# RPI-Lora-Gateway-Shield.net
KiCad netlist of a schematic drawn in EAGLE
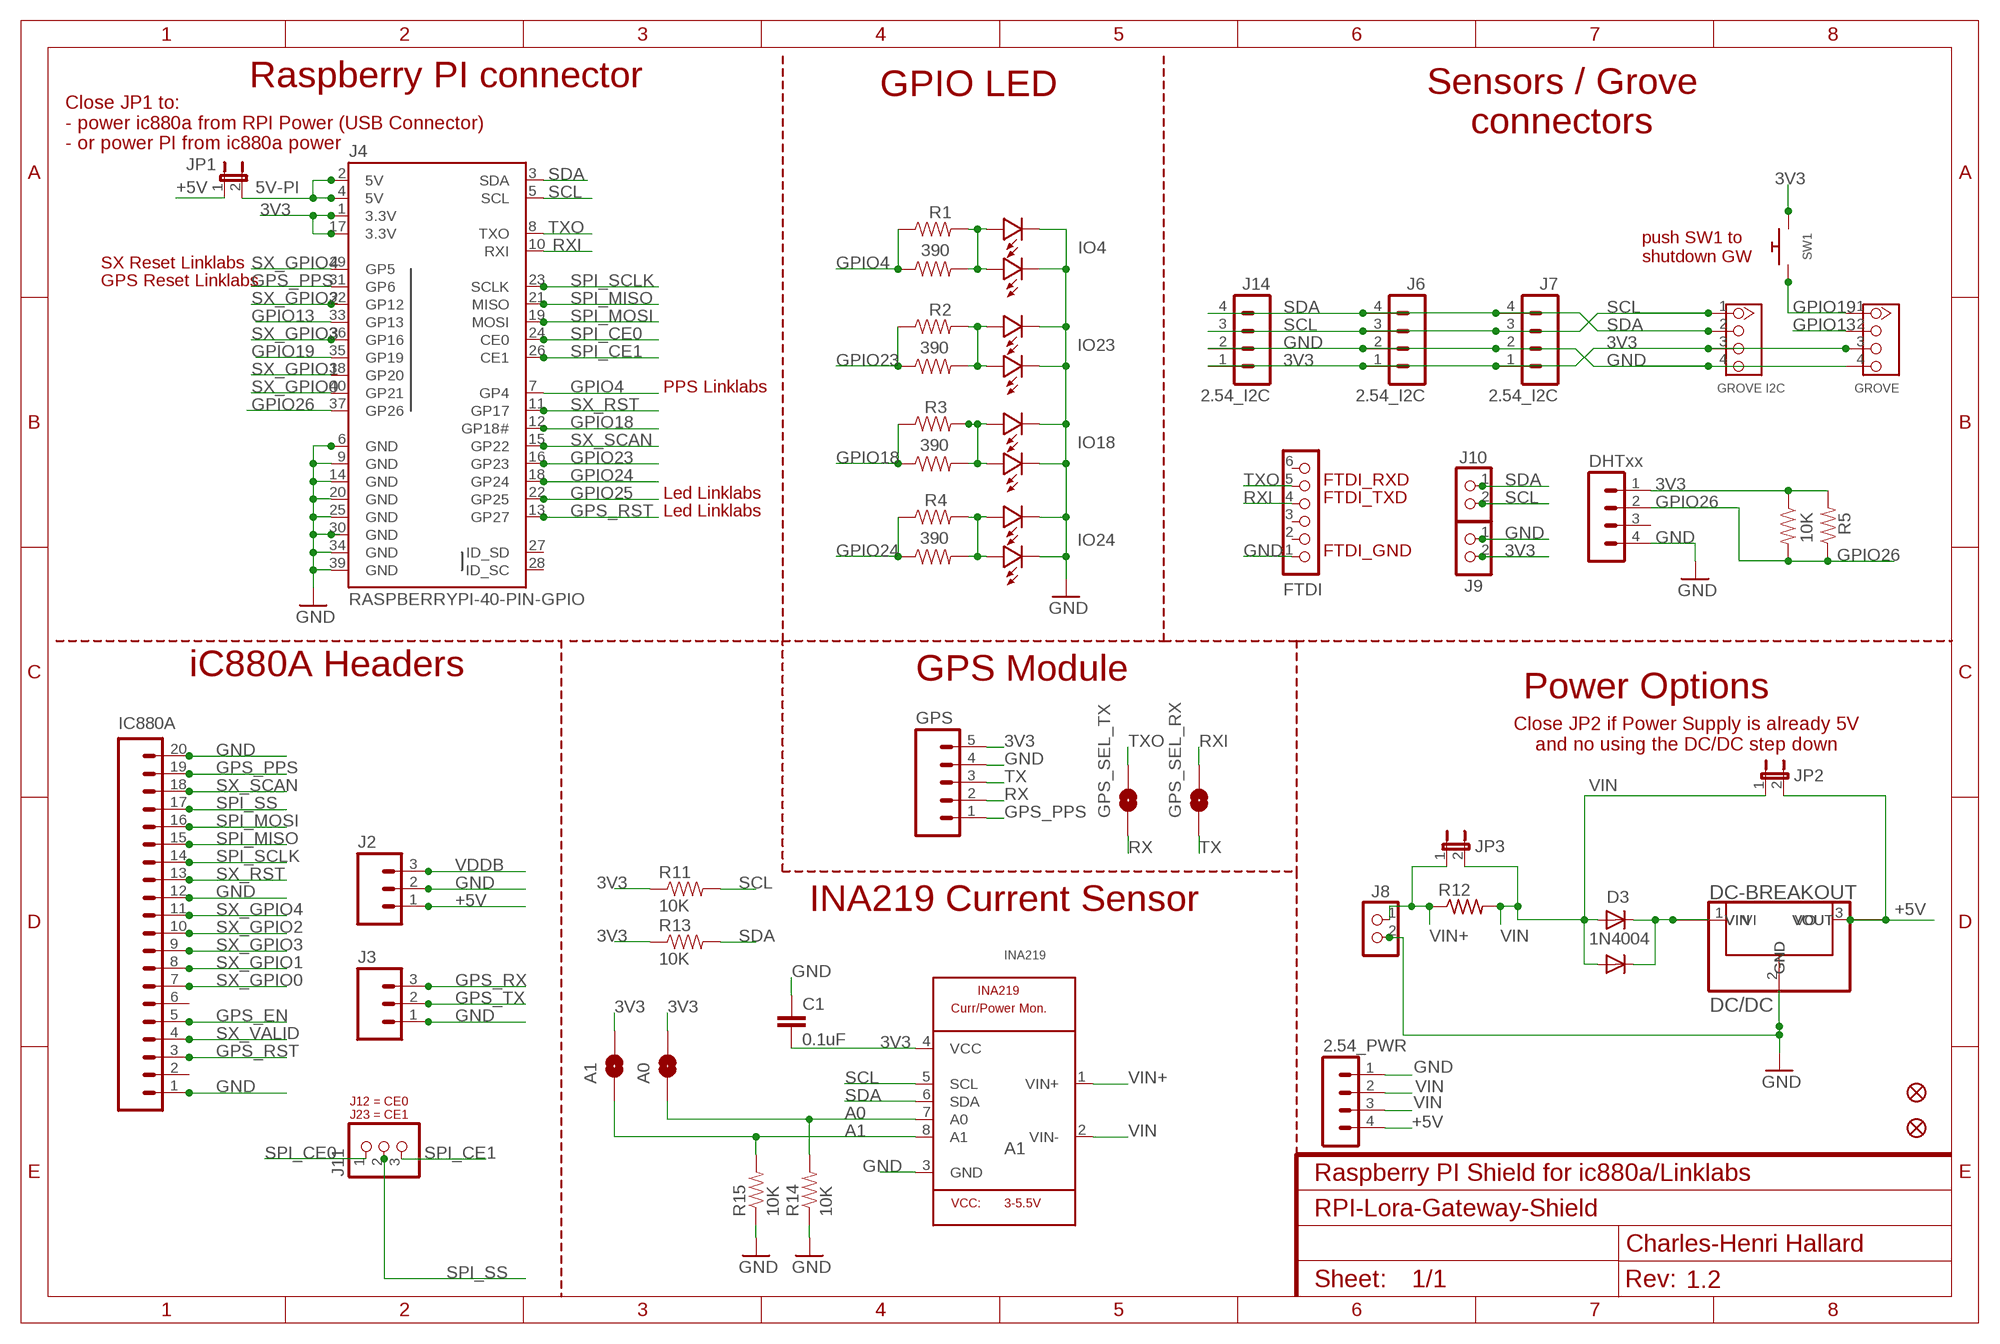
[diagram p0: schematic, sheet 1]

(export (version "E")
  (design (tool "Eeschema 10.0.6"))
  (components
    (comp (ref "A0")
      (value "SOLDERJUMPERNO")
      (footprint "eagle-import:SJ_2S-NO")
      (libsource (lib "eagle-import") (part "SOLDERJUMPERNO"))
    )
    (comp (ref "A1")
      (value "SOLDERJUMPERNO")
      (footprint "eagle-import:SJ_2S-NO")
      (libsource (lib "eagle-import") (part "SOLDERJUMPERNO"))
    )
    (comp (ref "C1")
      (value "0.1uF")
      (footprint "eagle-import:0805-CAP")
      (libsource (lib "eagle-import") (part "2.2UF-25V-+80/-20(0805)"))
    )
    (comp (ref "D3")
      (value "1N4004")
      (footprint "eagle-import:DO41-10")
      (libsource (lib "eagle-import") (part "1N4004"))
    )
    (comp (ref "D4")
      (value "1N4007")
      (footprint "eagle-import:DO-214AC")
      (libsource (lib "eagle-import") (part "DIODE-DO-214AC"))
    )
    (comp (ref "DC/DC")
      (value "DC-BREAKOUT")
      (footprint "eagle-import:DC-BREAKOUT")
      (libsource (lib "eagle-import") (part "DC-BREAKOUTSTD"))
    )
    (comp (ref "FID2")
      (value "FIDUCIAL\"\"")
      (footprint "eagle-import:FIDUCIAL_1MM")
      (libsource (lib "eagle-import") (part "FIDUCIAL{dblquote}{dblquote}"))
    )
    (comp (ref "FID3")
      (value "FIDUCIAL\"\"")
      (footprint "eagle-import:FIDUCIAL_1MM")
      (libsource (lib "eagle-import") (part "FIDUCIAL{dblquote}{dblquote}"))
    )
    (comp (ref "FTDI")
      (value "CON_HEADER_1X06-PTH")
      (footprint "eagle-import:M1X6")
      (libsource (lib "eagle-import") (part "CON_HEADER_1X06-PTH"))
    )
    (comp (ref "GPS")
      (value "M05PTH")
      (footprint "eagle-import:1X05")
      (libsource (lib "eagle-import") (part "M05PTH"))
    )
    (comp (ref "GPS_SEL_RX")
      (value "SOLDERJUMPERNO")
      (footprint "eagle-import:SJ_2S-NO")
      (libsource (lib "eagle-import") (part "SOLDERJUMPERNO"))
    )
    (comp (ref "GPS_SEL_TX")
      (value "SOLDERJUMPERNO")
      (footprint "eagle-import:SJ_2S-NO")
      (libsource (lib "eagle-import") (part "SOLDERJUMPERNO"))
    )
    (comp (ref "IC880A")
      (value "M20LOCK")
      (footprint "eagle-import:1X20_LOCK")
      (libsource (lib "eagle-import") (part "M20LOCK"))
    )
    (comp (ref "INA219")
      (value "INA219")
      (footprint "eagle-import:SOT23-8")
      (libsource (lib "eagle-import") (part "INA219"))
    )
    (comp (ref "J1")
      (value "GROVE")
      (footprint "eagle-import:HW4-2.0")
      (libsource (lib "eagle-import") (part "GROVE-CONNECTOR-DIP(4P-2.0)"))
    )
    (comp (ref "J2")
      (value "M03LOCK")
      (footprint "eagle-import:1X03_LOCK")
      (libsource (lib "eagle-import") (part "M03LOCK"))
    )
    (comp (ref "J3")
      (value "M03LOCK")
      (footprint "eagle-import:1X03_LOCK")
      (libsource (lib "eagle-import") (part "M03LOCK"))
    )
    (comp (ref "J4")
      (value "RASPBERRYPI-40-PIN-GPIO")
      (footprint "eagle-import:2X20-SHROUDED")
      (libsource (lib "eagle-import") (part "RASPBERRYPI-40-PIN-GPIO"))
    )
    (comp (ref "J5")
      (value "DHTxx")
      (footprint "eagle-import:1X04_NO_LOCK")
      (libsource (lib "eagle-import") (part "CON_HEADER_1X04'NO_LOCK'"))
    )
    (comp (ref "J6")
      (value "2.54_I2C")
      (footprint "eagle-import:1X04_NO_LOCK")
      (libsource (lib "eagle-import") (part "CON_HEADER_1X04'NO_LOCK'"))
    )
    (comp (ref "J7")
      (value "2.54_I2C")
      (footprint "eagle-import:1X04_NO_LOCK")
      (libsource (lib "eagle-import") (part "CON_HEADER_1X04'NO_LOCK'"))
    )
    (comp (ref "J8")
      (value "CON_TERMINAL_BLOCK_02-5MM")
      (footprint "eagle-import:TERMINAL_BLOCK_2P_5")
      (libsource (lib "eagle-import") (part "CON_TERMINAL_BLOCK_02-5MM"))
    )
    (comp (ref "J9")
      (value "CON_TERMINAL_BLOCK_02-5MM")
      (footprint "eagle-import:TERMINAL_BLOCK_2P_5")
      (libsource (lib "eagle-import") (part "CON_TERMINAL_BLOCK_02-5MM"))
    )
    (comp (ref "J10")
      (value "CON_TERMINAL_BLOCK_02-5MM")
      (footprint "eagle-import:TERMINAL_BLOCK_2P_5")
      (libsource (lib "eagle-import") (part "CON_TERMINAL_BLOCK_02-5MM"))
    )
    (comp (ref "J11")
      (value "JUMPER_1X30805")
      (footprint "eagle-import:JP3_0805")
      (fields
        (field (name "J12") "optA")
        (field (name "J23") "optB")
        (field (name "J12_1") "CE0")
        (field (name "J23_1") "CE1")
      )
      (libsource (lib "eagle-import") (part "JUMPER_1X30805"))
    )
    (comp (ref "J12")
      (value "2.54_PWR")
      (footprint "eagle-import:1X04_NO_LOCK")
      (libsource (lib "eagle-import") (part "CON_HEADER_1X04'NO_LOCK'"))
    )
    (comp (ref "J13")
      (value "GROVE I2C")
      (footprint "eagle-import:HW4-2.0")
      (libsource (lib "eagle-import") (part "GROVE-CONNECTOR-DIP(4P-2.0)"))
    )
    (comp (ref "J14")
      (value "2.54_I2C")
      (footprint "eagle-import:1X04_NO_LOCK")
      (libsource (lib "eagle-import") (part "CON_HEADER_1X04'NO_LOCK'"))
    )
    (comp (ref "JP1")
      (value "JUMPER2")
      (footprint "eagle-import:JUMPER2")
      (libsource (lib "eagle-import") (part "JUMPER2"))
    )
    (comp (ref "JP2")
      (value "JUMPER2")
      (footprint "eagle-import:JUMPER2")
      (libsource (lib "eagle-import") (part "JUMPER2"))
    )
    (comp (ref "JP3")
      (value "JUMPER2")
      (footprint "eagle-import:JUMPER2")
      (libsource (lib "eagle-import") (part "JUMPER2"))
    )
    (comp (ref "LED1")
      (value "LED0805")
      (footprint "eagle-import:0805-LED")
      (libsource (lib "eagle-import") (part "LED0805"))
    )
    (comp (ref "LED2")
      (value "LED0805")
      (footprint "eagle-import:0805-LED")
      (libsource (lib "eagle-import") (part "LED0805"))
    )
    (comp (ref "LED3")
      (value "LED0805")
      (footprint "eagle-import:0805-LED")
      (libsource (lib "eagle-import") (part "LED0805"))
    )
    (comp (ref "LED4")
      (value "LED0805")
      (footprint "eagle-import:0805-LED")
      (libsource (lib "eagle-import") (part "LED0805"))
    )
    (comp (ref "R1")
      (value "390")
      (footprint "eagle-import:AXIAL-0.4")
      (libsource (lib "eagle-import") (part "_c2h_RESISTORPTH-1/4W"))
    )
    (comp (ref "R2")
      (value "390")
      (footprint "eagle-import:AXIAL-0.4")
      (libsource (lib "eagle-import") (part "_c2h_RESISTORPTH-1/4W"))
    )
    (comp (ref "R3")
      (value "390")
      (footprint "eagle-import:AXIAL-0.4")
      (libsource (lib "eagle-import") (part "_c2h_RESISTORPTH-1/4W"))
    )
    (comp (ref "R4")
      (value "390")
      (footprint "eagle-import:AXIAL-0.4")
      (libsource (lib "eagle-import") (part "_c2h_RESISTORPTH-1/4W"))
    )
    (comp (ref "R5")
      (value "10K")
      (footprint "eagle-import:AXIAL-0.4")
      (libsource (lib "eagle-import") (part "_c2h_RESISTORPTH-1/4W"))
    )
    (comp (ref "R6")
      (value "RESISTOR0805-RES")
      (footprint "eagle-import:0805-RES")
      (libsource (lib "eagle-import") (part "_c2h_RESISTOR0805-RES"))
    )
    (comp (ref "R7")
      (value "RESISTOR0805-RES")
      (footprint "eagle-import:0805-RES")
      (libsource (lib "eagle-import") (part "_c2h_RESISTOR0805-RES"))
    )
    (comp (ref "R8")
      (value "RESISTOR0805-RES")
      (footprint "eagle-import:0805-RES")
      (libsource (lib "eagle-import") (part "_c2h_RESISTOR0805-RES"))
    )
    (comp (ref "R9")
      (value "RESISTOR0805-RES")
      (footprint "eagle-import:0805-RES")
      (libsource (lib "eagle-import") (part "_c2h_RESISTOR0805-RES"))
    )
    (comp (ref "R10")
      (value "RESISTOR0805-RES")
      (footprint "eagle-import:0805-RES")
      (libsource (lib "eagle-import") (part "_c2h_RESISTOR0805-RES"))
    )
    (comp (ref "R11")
      (value "10K")
      (footprint "eagle-import:0805")
      (libsource (lib "eagle-import") (part "RESISTOR0805-RES"))
    )
    (comp (ref "R12")
      (value "R-US_R2512")
      (footprint "eagle-import:R2512")
      (libsource (lib "eagle-import") (part "R-US_R2512"))
    )
    (comp (ref "R13")
      (value "10K")
      (footprint "eagle-import:0805")
      (libsource (lib "eagle-import") (part "RESISTOR0805-RES"))
    )
    (comp (ref "R14")
      (value "10K")
      (footprint "eagle-import:0805")
      (libsource (lib "eagle-import") (part "RESISTOR0805-RES"))
    )
    (comp (ref "R15")
      (value "10K")
      (footprint "eagle-import:0805")
      (libsource (lib "eagle-import") (part "RESISTOR0805-RES"))
    )
    (comp (ref "SW1")
      (value "SWITCH_PUSHBUTTONEVQ-PE")
      (footprint "eagle-import:TACT_PANA-EVQ")
      (libsource (lib "eagle-import") (part "SWITCH_PUSHBUTTONEVQ-PE"))
    )
    (comp (ref "U$4")
      (value "IO4")
      (footprint "eagle-import:LED3MM")
      (libsource (lib "eagle-import") (part "LED3MM"))
    )
    (comp (ref "U$5")
      (value "IO23")
      (footprint "eagle-import:LED3MM")
      (libsource (lib "eagle-import") (part "LED3MM"))
    )
    (comp (ref "U$6")
      (value "IO18")
      (footprint "eagle-import:LED3MM")
      (libsource (lib "eagle-import") (part "LED3MM"))
    )
    (comp (ref "U$7")
      (value "IO24")
      (footprint "eagle-import:LED3MM")
      (libsource (lib "eagle-import") (part "LED3MM"))
    )
    (comp (ref "U$8")
      (value "DC-BREAKOUTFIXED")
      (footprint "eagle-import:DC-DC-FIXED")
      (libsource (lib "eagle-import") (part "DC-BREAKOUTFIXED"))
    )
    (comp (ref "U$11")
      (value "OKI-78SR")
      (footprint "eagle-import:OKI-78SRH")
      (libsource (lib "eagle-import") (part "DCDC_OKI-78SRHORZ"))
    )
  )
  (nets
    (net (code "1") (name "/+5V") (class "Default")
      (node (ref "DC/DC") (pin "VOUT-1") (pinfunction "VOUT_VOUT-1") (pintype "output"))
      (node (ref "DC/DC") (pin "VOUT-2") (pinfunction "VOUT_VOUT-2") (pintype "output"))
      (node (ref "J12") (pin "4") (pinfunction "4_4") (pintype "passive"))
      (node (ref "J2") (pin "1") (pinfunction "1_1") (pintype "passive"))
      (node (ref "JP1") (pin "1") (pinfunction "1_1") (pintype "passive"))
      (node (ref "JP2") (pin "2") (pinfunction "2_2") (pintype "passive"))
      (node (ref "U$11") (pin "3") (pinfunction "VO_3") (pintype "bidirectional"))
      (node (ref "U$8") (pin "VOUT-1") (pinfunction "VOUT_VOUT-1") (pintype "output"))
      (node (ref "U$8") (pin "VOUT-2") (pinfunction "VOUT_VOUT-2") (pintype "output"))
    )
    (net (code "2") (name "/3V3") (class "Default")
      (node (ref "A0") (pin "2") (pinfunction "2_2") (pintype "passive"))
      (node (ref "A1") (pin "2") (pinfunction "2_2") (pintype "passive"))
      (node (ref "C1") (pin "2") (pinfunction "2_2") (pintype "passive"))
      (node (ref "GPS") (pin "5") (pinfunction "5_5") (pintype "passive"))
      (node (ref "INA219") (pin "4") (pinfunction "VCC_4") (pintype "bidirectional"))
      (node (ref "J1") (pin "3") (pinfunction "3_3") (pintype "bidirectional"))
      (node (ref "J13") (pin "3") (pinfunction "3_3") (pintype "bidirectional"))
      (node (ref "J14") (pin "1") (pinfunction "1_1") (pintype "passive"))
      (node (ref "J4") (pin "1") (pinfunction "3.3V_1") (pintype "power_in"))
      (node (ref "J4") (pin "17") (pinfunction "3.3V_17") (pintype "power_in"))
      (node (ref "J5") (pin "1") (pinfunction "1_1") (pintype "passive"))
      (node (ref "J6") (pin "1") (pinfunction "1_1") (pintype "passive"))
      (node (ref "J7") (pin "1") (pinfunction "1_1") (pintype "passive"))
      (node (ref "J9") (pin "2") (pinfunction "2_2") (pintype "passive"))
      (node (ref "R10") (pin "2") (pinfunction "2_2") (pintype "passive"))
      (node (ref "R11") (pin "1") (pinfunction "1_1") (pintype "passive"))
      (node (ref "R13") (pin "1") (pinfunction "1_1") (pintype "passive"))
      (node (ref "R5") (pin "P$1") (pinfunction "1_P$1") (pintype "passive"))
      (node (ref "SW1") (pin "P$2") (pinfunction "P$2_P$2") (pintype "passive"))
    )
    (net (code "3") (name "/5V-PI") (class "Default")
      (node (ref "J4") (pin "2") (pinfunction "5V_2") (pintype "power_in"))
      (node (ref "J4") (pin "4") (pinfunction "5V_4") (pintype "power_in"))
      (node (ref "JP1") (pin "2") (pinfunction "2_2") (pintype "passive"))
    )
    (net (code "4") (name "/A0") (class "Default")
      (node (ref "A0") (pin "1") (pinfunction "1_1") (pintype "passive"))
      (node (ref "INA219") (pin "7") (pinfunction "A0_7") (pintype "bidirectional"))
      (node (ref "R14") (pin "2") (pinfunction "2_2") (pintype "passive"))
    )
    (net (code "5") (name "/A1") (class "Default")
      (node (ref "A1") (pin "1") (pinfunction "1_1") (pintype "passive"))
      (node (ref "INA219") (pin "8") (pinfunction "A1_8") (pintype "bidirectional"))
      (node (ref "R15") (pin "2") (pinfunction "2_2") (pintype "passive"))
    )
    (net (code "6") (name "/GPIO4") (class "Default")
      (node (ref "J4") (pin "7") (pinfunction "GP4_7") (pintype "bidirectional"))
      (node (ref "R1") (pin "P$1") (pinfunction "1_P$1") (pintype "passive"))
      (node (ref "R6") (pin "1") (pinfunction "1_1") (pintype "passive"))
    )
    (net (code "7") (name "/GPIO13") (class "Default")
      (node (ref "J1") (pin "2") (pinfunction "2_2") (pintype "bidirectional"))
      (node (ref "J4") (pin "33") (pinfunction "GP13_33") (pintype "bidirectional"))
    )
    (net (code "8") (name "/GPIO18") (class "Default")
      (node (ref "J4") (pin "12") (pinfunction "GP18#_12") (pintype "bidirectional"))
      (node (ref "R3") (pin "P$1") (pinfunction "1_P$1") (pintype "passive"))
      (node (ref "R8") (pin "1") (pinfunction "1_1") (pintype "passive"))
    )
    (net (code "9") (name "/GPIO19") (class "Default")
      (node (ref "J1") (pin "1") (pinfunction "1_1") (pintype "bidirectional"))
      (node (ref "J4") (pin "35") (pinfunction "GP19_35") (pintype "bidirectional"))
      (node (ref "SW1") (pin "P$1") (pinfunction "P$1_P$1") (pintype "passive"))
    )
    (net (code "10") (name "/GPIO23") (class "Default")
      (node (ref "J4") (pin "16") (pinfunction "GP23_16") (pintype "bidirectional"))
      (node (ref "R2") (pin "P$1") (pinfunction "1_P$1") (pintype "passive"))
      (node (ref "R7") (pin "1") (pinfunction "1_1") (pintype "passive"))
    )
    (net (code "11") (name "/GPIO24") (class "Default")
      (node (ref "J4") (pin "18") (pinfunction "GP24_18") (pintype "bidirectional"))
      (node (ref "R4") (pin "P$1") (pinfunction "1_P$1") (pintype "passive"))
      (node (ref "R9") (pin "1") (pinfunction "1_1") (pintype "passive"))
    )
    (net (code "12") (name "/GPIO25") (class "Default")
      (node (ref "J4") (pin "22") (pinfunction "GP25_22") (pintype "bidirectional"))
    )
    (net (code "13") (name "/GPIO26") (class "Default")
      (node (ref "J4") (pin "37") (pinfunction "GP26_37") (pintype "bidirectional"))
      (node (ref "J5") (pin "2") (pinfunction "2_2") (pintype "passive"))
      (node (ref "R10") (pin "1") (pinfunction "1_1") (pintype "passive"))
      (node (ref "R5") (pin "P$2") (pinfunction "2_P$2") (pintype "passive"))
    )
    (net (code "14") (name "/GPS_EN") (class "Default")
      (node (ref "IC880A") (pin "5") (pinfunction "5_5") (pintype "passive"))
    )
    (net (code "15") (name "/GPS_PPS") (class "Default")
      (node (ref "GPS") (pin "1") (pinfunction "1_1") (pintype "passive"))
      (node (ref "IC880A") (pin "19") (pinfunction "19_19") (pintype "passive"))
      (node (ref "J4") (pin "31") (pinfunction "GP6_31") (pintype "bidirectional"))
    )
    (net (code "16") (name "/GPS_RST") (class "Default")
      (node (ref "IC880A") (pin "3") (pinfunction "3_3") (pintype "passive"))
      (node (ref "J4") (pin "13") (pinfunction "GP27_13") (pintype "bidirectional"))
    )
    (net (code "17") (name "/GPS_RX") (class "Default")
      (node (ref "J3") (pin "3") (pinfunction "3_3") (pintype "passive"))
    )
    (net (code "18") (name "/GPS_TX") (class "Default")
      (node (ref "J3") (pin "2") (pinfunction "2_2") (pintype "passive"))
    )
    (net (code "19") (name "/RX") (class "Default")
      (node (ref "GPS") (pin "2") (pinfunction "2_2") (pintype "passive"))
      (node (ref "GPS_SEL_TX") (pin "1") (pinfunction "1_1") (pintype "passive"))
    )
    (net (code "20") (name "/RXI") (class "Default")
      (node (ref "FTDI") (pin "4") (pinfunction "4_4") (pintype "passive"))
      (node (ref "GPS_SEL_RX") (pin "2") (pinfunction "2_2") (pintype "passive"))
      (node (ref "J4") (pin "10") (pinfunction "RXI_10") (pintype "input"))
    )
    (net (code "21") (name "/SCL") (class "Default")
      (node (ref "INA219") (pin "5") (pinfunction "SCL_5") (pintype "bidirectional"))
      (node (ref "J10") (pin "2") (pinfunction "2_2") (pintype "passive"))
      (node (ref "J13") (pin "1") (pinfunction "1_1") (pintype "bidirectional"))
      (node (ref "J14") (pin "3") (pinfunction "3_3") (pintype "passive"))
      (node (ref "J4") (pin "5") (pinfunction "SCL_5") (pintype "bidirectional"))
      (node (ref "J6") (pin "3") (pinfunction "3_3") (pintype "passive"))
      (node (ref "J7") (pin "3") (pinfunction "3_3") (pintype "passive"))
      (node (ref "R11") (pin "2") (pinfunction "2_2") (pintype "passive"))
    )
    (net (code "22") (name "/SDA") (class "Default")
      (node (ref "INA219") (pin "6") (pinfunction "SDA_6") (pintype "bidirectional"))
      (node (ref "J10") (pin "1") (pinfunction "1_1") (pintype "passive"))
      (node (ref "J13") (pin "2") (pinfunction "2_2") (pintype "bidirectional"))
      (node (ref "J14") (pin "4") (pinfunction "4_4") (pintype "passive"))
      (node (ref "J4") (pin "3") (pinfunction "SDA_3") (pintype "bidirectional"))
      (node (ref "J6") (pin "4") (pinfunction "4_4") (pintype "passive"))
      (node (ref "J7") (pin "4") (pinfunction "4_4") (pintype "passive"))
      (node (ref "R13") (pin "2") (pinfunction "2_2") (pintype "passive"))
    )
    (net (code "23") (name "/SPI_CE0") (class "Default")
      (node (ref "J11") (pin "1") (pinfunction "1_1") (pintype "passive"))
      (node (ref "J4") (pin "24") (pinfunction "CE0_24") (pintype "output"))
    )
    (net (code "24") (name "/SPI_CE1") (class "Default")
      (node (ref "J11") (pin "3") (pinfunction "3_3") (pintype "passive"))
      (node (ref "J4") (pin "26") (pinfunction "CE1_26") (pintype "output"))
    )
    (net (code "25") (name "/SPI_MISO") (class "Default")
      (node (ref "IC880A") (pin "15") (pinfunction "15_15") (pintype "passive"))
      (node (ref "J4") (pin "21") (pinfunction "MISO_21") (pintype "input"))
    )
    (net (code "26") (name "/SPI_MOSI") (class "Default")
      (node (ref "IC880A") (pin "16") (pinfunction "16_16") (pintype "passive"))
      (node (ref "J4") (pin "19") (pinfunction "MOSI_19") (pintype "output"))
    )
    (net (code "27") (name "/SPI_SCLK") (class "Default")
      (node (ref "IC880A") (pin "14") (pinfunction "14_14") (pintype "passive"))
      (node (ref "J4") (pin "23") (pinfunction "SCLK_23") (pintype "output"))
    )
    (net (code "28") (name "/SPI_SS") (class "Default")
      (node (ref "IC880A") (pin "17") (pinfunction "17_17") (pintype "passive"))
      (node (ref "J11") (pin "2") (pinfunction "2_2") (pintype "passive"))
    )
    (net (code "29") (name "/SX_GPIO0") (class "Default")
      (node (ref "IC880A") (pin "7") (pinfunction "7_7") (pintype "passive"))
      (node (ref "J4") (pin "40") (pinfunction "GP21_40") (pintype "bidirectional"))
    )
    (net (code "30") (name "/SX_GPIO1") (class "Default")
      (node (ref "IC880A") (pin "8") (pinfunction "8_8") (pintype "passive"))
      (node (ref "J4") (pin "38") (pinfunction "GP20_38") (pintype "bidirectional"))
    )
    (net (code "31") (name "/SX_GPIO2") (class "Default")
      (node (ref "IC880A") (pin "10") (pinfunction "10_10") (pintype "passive"))
      (node (ref "J4") (pin "32") (pinfunction "GP12_32") (pintype "bidirectional"))
    )
    (net (code "32") (name "/SX_GPIO3") (class "Default")
      (node (ref "IC880A") (pin "9") (pinfunction "9_9") (pintype "passive"))
      (node (ref "J4") (pin "36") (pinfunction "GP16_36") (pintype "bidirectional"))
    )
    (net (code "33") (name "/SX_GPIO4") (class "Default")
      (node (ref "IC880A") (pin "11") (pinfunction "11_11") (pintype "passive"))
      (node (ref "J4") (pin "29") (pinfunction "GP5_29") (pintype "bidirectional"))
    )
    (net (code "34") (name "/SX_RST") (class "Default")
      (node (ref "IC880A") (pin "13") (pinfunction "13_13") (pintype "passive"))
      (node (ref "J4") (pin "11") (pinfunction "GP17_11") (pintype "bidirectional"))
    )
    (net (code "35") (name "/SX_SCAN") (class "Default")
      (node (ref "IC880A") (pin "18") (pinfunction "18_18") (pintype "passive"))
      (node (ref "J4") (pin "15") (pinfunction "GP22_15") (pintype "bidirectional"))
    )
    (net (code "36") (name "/SX_VALID") (class "Default")
      (node (ref "IC880A") (pin "4") (pinfunction "4_4") (pintype "passive"))
    )
    (net (code "37") (name "/TX") (class "Default")
      (node (ref "GPS") (pin "3") (pinfunction "3_3") (pintype "passive"))
      (node (ref "GPS_SEL_RX") (pin "1") (pinfunction "1_1") (pintype "passive"))
    )
    (net (code "38") (name "/TXO") (class "Default")
      (node (ref "FTDI") (pin "5") (pinfunction "5_5") (pintype "passive"))
      (node (ref "GPS_SEL_TX") (pin "2") (pinfunction "2_2") (pintype "passive"))
      (node (ref "J4") (pin "8") (pinfunction "TXO_8") (pintype "output"))
    )
    (net (code "39") (name "/VDDB") (class "Default")
      (node (ref "J2") (pin "3") (pinfunction "3_3") (pintype "passive"))
    )
    (net (code "40") (name "/VIN") (class "Default")
      (node (ref "D3") (pin "A") (pinfunction "A_A") (pintype "passive"))
      (node (ref "D4") (pin "2") (pinfunction "A_2") (pintype "passive"))
      (node (ref "INA219") (pin "2") (pinfunction "VIN-_2") (pintype "bidirectional"))
      (node (ref "J12") (pin "2") (pinfunction "2_2") (pintype "passive"))
      (node (ref "J12") (pin "3") (pinfunction "3_3") (pintype "passive"))
      (node (ref "JP2") (pin "1") (pinfunction "1_1") (pintype "passive"))
      (node (ref "JP3") (pin "2") (pinfunction "2_2") (pintype "passive"))
      (node (ref "R12") (pin "2") (pinfunction "2_2") (pintype "passive"))
    )
    (net (code "41") (name "/VIN+") (class "Default")
      (node (ref "INA219") (pin "1") (pinfunction "VIN+_1") (pintype "bidirectional"))
      (node (ref "J8") (pin "1") (pinfunction "1_1") (pintype "passive"))
      (node (ref "JP3") (pin "1") (pinfunction "1_1") (pintype "passive"))
      (node (ref "R12") (pin "1") (pinfunction "1_1") (pintype "passive"))
    )
    (net (code "42") (name "GND") (class "Default")
      (node (ref "C1") (pin "1") (pinfunction "1_1") (pintype "passive"))
      (node (ref "DC/DC") (pin "GND-1") (pinfunction "GND_GND-1") (pintype "passive"))
      (node (ref "DC/DC") (pin "GND-2") (pinfunction "GND_GND-2") (pintype "passive"))
      (node (ref "DC/DC") (pin "GND-3") (pinfunction "GND_GND-3") (pintype "passive"))
      (node (ref "DC/DC") (pin "GND-4") (pinfunction "GND_GND-4") (pintype "passive"))
      (node (ref "FTDI") (pin "1") (pinfunction "1_1") (pintype "bidirectional"))
      (node (ref "GPS") (pin "4") (pinfunction "4_4") (pintype "passive"))
      (node (ref "IC880A") (pin "1") (pinfunction "1_1") (pintype "passive"))
      (node (ref "IC880A") (pin "12") (pinfunction "12_12") (pintype "passive"))
      (node (ref "IC880A") (pin "20") (pinfunction "20_20") (pintype "passive"))
      (node (ref "INA219") (pin "3") (pinfunction "GND_3") (pintype "bidirectional"))
      (node (ref "J1") (pin "4") (pinfunction "4_4") (pintype "bidirectional"))
      (node (ref "J12") (pin "1") (pinfunction "1_1") (pintype "passive"))
      (node (ref "J13") (pin "4") (pinfunction "4_4") (pintype "bidirectional"))
      (node (ref "J14") (pin "2") (pinfunction "2_2") (pintype "passive"))
      (node (ref "J2") (pin "2") (pinfunction "2_2") (pintype "passive"))
      (node (ref "J3") (pin "1") (pinfunction "1_1") (pintype "passive"))
      (node (ref "J4") (pin "14") (pinfunction "GND_14") (pintype "power_in"))
      (node (ref "J4") (pin "20") (pinfunction "GND_20") (pintype "power_in"))
      (node (ref "J4") (pin "25") (pinfunction "GND_25") (pintype "power_in"))
      (node (ref "J4") (pin "30") (pinfunction "GND_30") (pintype "power_in"))
      (node (ref "J4") (pin "34") (pinfunction "GND_34") (pintype "power_in"))
      (node (ref "J4") (pin "39") (pinfunction "GND_39") (pintype "power_in"))
      (node (ref "J4") (pin "6") (pinfunction "GND_6") (pintype "power_in"))
      (node (ref "J4") (pin "9") (pinfunction "GND_9") (pintype "power_in"))
      (node (ref "J5") (pin "4") (pinfunction "4_4") (pintype "passive"))
      (node (ref "J6") (pin "2") (pinfunction "2_2") (pintype "passive"))
      (node (ref "J7") (pin "2") (pinfunction "2_2") (pintype "passive"))
      (node (ref "J8") (pin "2") (pinfunction "2_2") (pintype "passive"))
      (node (ref "J9") (pin "1") (pinfunction "1_1") (pintype "passive"))
      (node (ref "LED1") (pin "MINUS") (pinfunction "MINUS_MINUS") (pintype "passive"))
      (node (ref "LED2") (pin "MINUS") (pinfunction "MINUS_MINUS") (pintype "passive"))
      (node (ref "LED3") (pin "MINUS") (pinfunction "MINUS_MINUS") (pintype "passive"))
      (node (ref "LED4") (pin "MINUS") (pinfunction "MINUS_MINUS") (pintype "passive"))
      (node (ref "R14") (pin "1") (pinfunction "1_1") (pintype "passive"))
      (node (ref "R15") (pin "1") (pinfunction "1_1") (pintype "passive"))
      (node (ref "U$11") (pin "2") (pinfunction "GND_2") (pintype "bidirectional"))
      (node (ref "U$4") (pin "MINUS") (pinfunction "MINUS_MINUS") (pintype "passive"))
      (node (ref "U$5") (pin "MINUS") (pinfunction "MINUS_MINUS") (pintype "passive"))
      (node (ref "U$6") (pin "MINUS") (pinfunction "MINUS_MINUS") (pintype "passive"))
      (node (ref "U$7") (pin "MINUS") (pinfunction "MINUS_MINUS") (pintype "passive"))
      (node (ref "U$8") (pin "GND-1") (pinfunction "GND_GND-1") (pintype "passive"))
      (node (ref "U$8") (pin "GND-2") (pinfunction "GND_GND-2") (pintype "passive"))
      (node (ref "U$8") (pin "GND-3") (pinfunction "GND_GND-3") (pintype "passive"))
      (node (ref "U$8") (pin "GND-4") (pinfunction "GND_GND-4") (pintype "passive"))
    )
    (net (code "43") (name "Net-(D4-C)") (class "Default")
      (node (ref "D3") (pin "C") (pinfunction "C_C") (pintype "passive"))
      (node (ref "D4") (pin "1") (pinfunction "C_1") (pintype "passive"))
      (node (ref "DC/DC") (pin "VIN-1") (pinfunction "VIN_VIN-1") (pintype "input"))
      (node (ref "DC/DC") (pin "VIN-2") (pinfunction "VIN_VIN-2") (pintype "input"))
      (node (ref "U$11") (pin "1") (pinfunction "VI_1") (pintype "bidirectional"))
      (node (ref "U$8") (pin "VIN-1") (pinfunction "VIN_VIN-1") (pintype "input"))
      (node (ref "U$8") (pin "VIN-2") (pinfunction "VIN_VIN-2") (pintype "input"))
    )
    (net (code "44") (name "Net-(R1-2)") (class "Default")
      (node (ref "LED1") (pin "PLUS") (pinfunction "PLUS_PLUS") (pintype "passive"))
      (node (ref "R1") (pin "P$2") (pinfunction "2_P$2") (pintype "passive"))
      (node (ref "R6") (pin "2") (pinfunction "2_2") (pintype "passive"))
      (node (ref "U$4") (pin "PLUS") (pinfunction "PLUS_PLUS") (pintype "passive"))
    )
    (net (code "45") (name "Net-(R2-2)") (class "Default")
      (node (ref "LED2") (pin "PLUS") (pinfunction "PLUS_PLUS") (pintype "passive"))
      (node (ref "R2") (pin "P$2") (pinfunction "2_P$2") (pintype "passive"))
      (node (ref "R7") (pin "2") (pinfunction "2_2") (pintype "passive"))
      (node (ref "U$5") (pin "PLUS") (pinfunction "PLUS_PLUS") (pintype "passive"))
    )
    (net (code "46") (name "Net-(R3-2)") (class "Default")
      (node (ref "LED3") (pin "PLUS") (pinfunction "PLUS_PLUS") (pintype "passive"))
      (node (ref "R3") (pin "P$2") (pinfunction "2_P$2") (pintype "passive"))
      (node (ref "R8") (pin "2") (pinfunction "2_2") (pintype "passive"))
      (node (ref "U$6") (pin "PLUS") (pinfunction "PLUS_PLUS") (pintype "passive"))
    )
    (net (code "47") (name "Net-(R4-2)") (class "Default")
      (node (ref "LED4") (pin "PLUS") (pinfunction "PLUS_PLUS") (pintype "passive"))
      (node (ref "R4") (pin "P$2") (pinfunction "2_P$2") (pintype "passive"))
      (node (ref "R9") (pin "2") (pinfunction "2_2") (pintype "passive"))
      (node (ref "U$7") (pin "PLUS") (pinfunction "PLUS_PLUS") (pintype "passive"))
    )
    (net (code "48") (name "unconnected-(FTDI-Pad2)") (class "Default")
      (node (ref "FTDI") (pin "2") (pinfunction "2_2") (pintype "bidirectional"))
    )
    (net (code "49") (name "unconnected-(FTDI-Pad3)") (class "Default")
      (node (ref "FTDI") (pin "3") (pinfunction "3_3") (pintype "passive"))
    )
    (net (code "50") (name "unconnected-(FTDI-Pad6)") (class "Default")
      (node (ref "FTDI") (pin "6") (pinfunction "6_6") (pintype "passive"))
    )
    (net (code "51") (name "unconnected-(IC880A-Pad2)") (class "Default")
      (node (ref "IC880A") (pin "2") (pinfunction "2_2") (pintype "passive"))
    )
    (net (code "52") (name "unconnected-(IC880A-Pad6)") (class "Default")
      (node (ref "IC880A") (pin "6") (pinfunction "6_6") (pintype "passive"))
    )
    (net (code "53") (name "unconnected-(J4-ID_SC-Pad28)") (class "Default")
      (node (ref "J4") (pin "28") (pinfunction "ID_SC_28") (pintype "bidirectional"))
    )
    (net (code "54") (name "unconnected-(J4-ID_SD-Pad27)") (class "Default")
      (node (ref "J4") (pin "27") (pinfunction "ID_SD_27") (pintype "bidirectional"))
    )
    (net (code "55") (name "unconnected-(J5-Pad3)") (class "Default")
      (node (ref "J5") (pin "3") (pinfunction "3_3") (pintype "passive"))
    )
  )
)
